# Sensor.net
KiCad netlist of a schematic drawn in Altium Designer
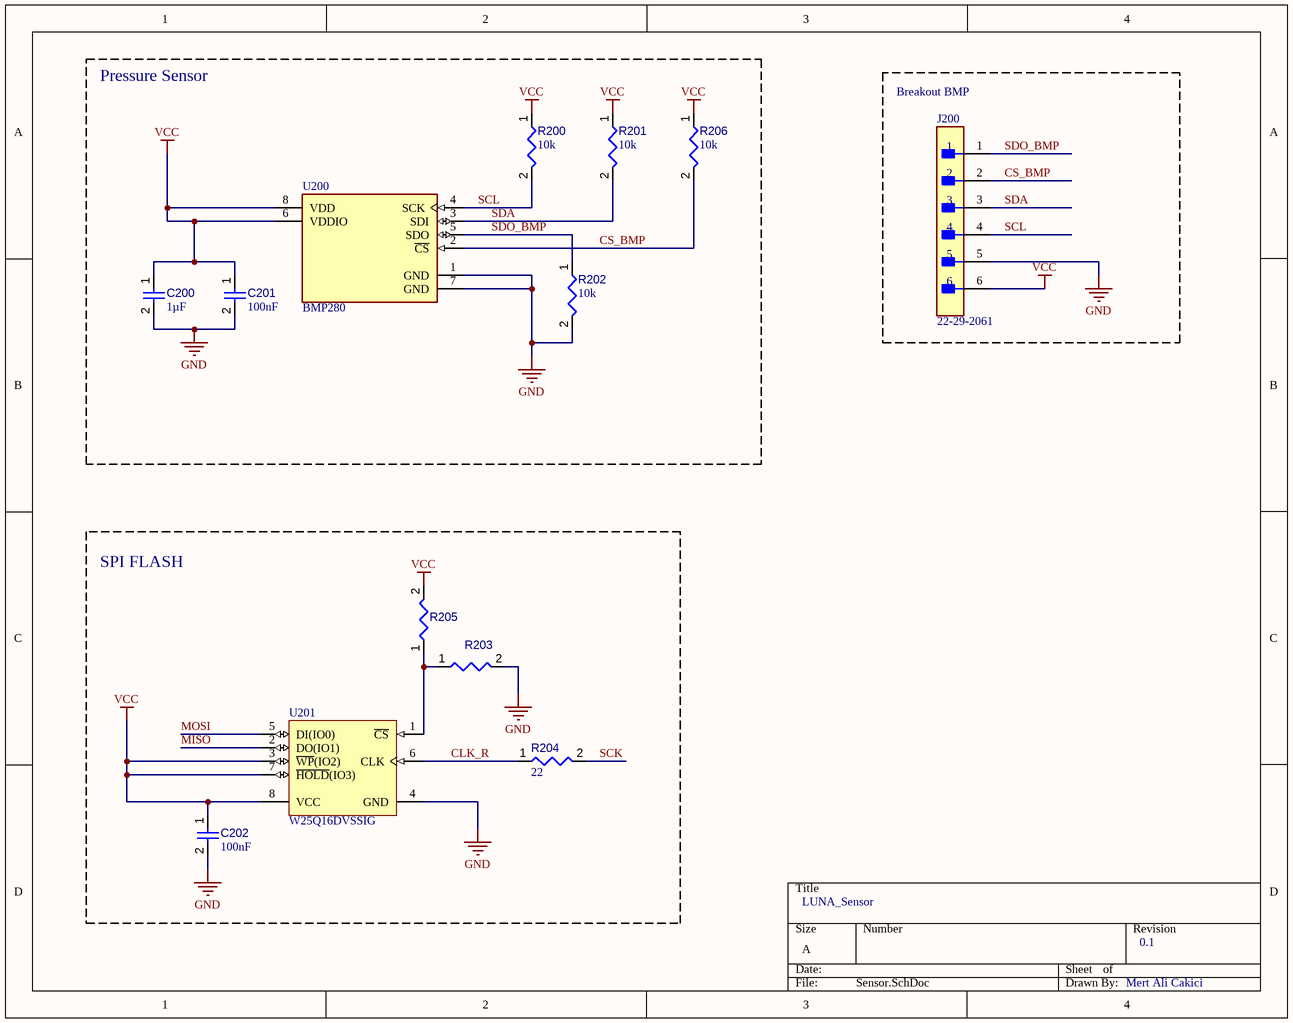
[diagram p0: Sensor.SchDoc]

(export (version "E")
  (design (tool "Eeschema 10.0.6"))
  (components
    (comp (ref "C200")
      (value "1µF")
      (footprint "CAPC1608X90X35NL15T15")
      (description "Chip Capacitor, 1 uF, +/- 10%, 16 V, 0603 (1608 Metric)")
      (fields (field (name "TOLERANCE") "10%") (field (name "Comment") "Capacitor 1uF +/- 10% 16V 0603"))
      (libsource (lib "Mert ALi Çakıcı") (part "CAP-NP-2"))
    )
    (comp (ref "C201")
      (value "100nF")
      (footprint "CAPC1608X90X40NL10T20")
      (description "Chip Capacitor, 100 nF, +/- 10%, 50 V, 0603 (1608 Metric)")
      (fields (field (name "TOLERANCE") "10%") (field (name "Comment") "Capacitor 100 nF +/-10% 50 V 0603"))
      (libsource (lib "Mert ALi Çakıcı") (part "CAP-NP-2"))
    )
    (comp (ref "C202")
      (value "100nF")
      (footprint "CAPC1608X90X40NL10T20")
      (description "Chip Capacitor, 100 nF, +/- 10%, 50 V, 0603 (1608 Metric)")
      (fields (field (name "TOLERANCE") "10%") (field (name "Comment") "Capacitor 100 nF +/-10% 50 V 0603"))
      (libsource (lib "Mert ALi Çakıcı") (part "CAP-NP-2"))
    )
    (comp (ref "J200")
      (value "22-29-2061")
      (footprint "FP-22-29-2061-MFG")
      (description "CONN HEADER VERT 6POS 2.54MM")
      (libsource (lib "Altium Content Vault") (part "f2cb566baf1c37ab5a3b8e90bbeafd6"))
    )
    (comp (ref "R200")
      (value "10k")
      (footprint "RESC1608X55X25NL10T15")
      (description "Chip Resistor, 10 KOhm, +/- 1%, 01 W, -55 to 155 degC, 0603 (1608 Metric)")
      (fields (field (name "POWER") "100mW") (field (name "TOLERANCE") "1%"))
      (libsource (lib "Mert ALi Çakıcı") (part "RES-2"))
    )
    (comp (ref "R201")
      (value "10k")
      (footprint "RESC1608X55X25NL10T15")
      (description "Chip Resistor, 10 KOhm, +/- 1%, 01 W, -55 to 155 degC, 0603 (1608 Metric)")
      (fields (field (name "POWER") "100mW") (field (name "TOLERANCE") "1%"))
      (libsource (lib "Mert ALi Çakıcı") (part "RES-2"))
    )
    (comp (ref "R202")
      (value "10k")
      (footprint "RESC1608X55X25NL10T15")
      (description "Chip Resistor, 10 KOhm, +/- 1%, 01 W, -55 to 155 degC, 0603 (1608 Metric)")
      (fields (field (name "POWER") "100mW") (field (name "TOLERANCE") "1%"))
      (libsource (lib "Mert ALi Çakıcı") (part "RES-2"))
    )
    (comp (ref "R203")
      (value "Jumper 0603")
      (footprint "RESC0603(1608)_L")
      (libsource (lib "Mert ALi Çakıcı") (part "RES-2"))
    )
    (comp (ref "R204")
      (value "22")
      (footprint "RESC1609X50X30ML08T20")
      (description "Chip Resistor, 22 Ohm, +/- 1%, 100 mW, -55 to 155 degC, 0603 (1608 Metric)")
      (fields (field (name "POWER") "100mW") (field (name "TOLERANCE") "1%"))
      (libsource (lib "Mert ALi Çakıcı") (part "RES-2"))
    )
    (comp (ref "R205")
      (value "DNP")
      (footprint "RESC0603(1608)_L")
      (description "Jumper 0603")
      (libsource (lib "Mert ALi Çakıcı") (part "RES-2"))
    )
    (comp (ref "R206")
      (value "10k")
      (footprint "RESC1608X55X25NL10T15")
      (description "Chip Resistor, 10 KOhm, +/- 1%, 01 W, -55 to 155 degC, 0603 (1608 Metric)")
      (fields (field (name "POWER") "100mW") (field (name "TOLERANCE") "1%"))
      (libsource (lib "Mert ALi Çakıcı") (part "RES-2"))
    )
    (comp (ref "U200")
      (value "BMP280")
      (footprint "FP-BMP280-MFG")
      (description "SENSOR PRESSURE ABS")
      (libsource (lib "Altium Content Vault") (part "69b1aacbb03d82763a43fac02afba64"))
    )
    (comp (ref "U201")
      (value "W25Q16DVSSIG")
      (footprint "WINB-W25Q16DVSSIG-8_N")
      (description "IC FLASH 16MBIT 104MHZ 8SOIC")
      (fields (field (name "MANUFACTURER") "Winbond"))
      (libsource (lib "Altium Content Vault") (part "WINB-W25Q16DVSSIG-8"))
    )
  )
  (nets
    (net (code "1") (name "/CLK_R") (class "Default")
      (node (ref "R204") (pin "1") (pinfunction "1_1") (pintype "passive"))
      (node (ref "U201") (pin "6") (pinfunction "CLK_6") (pintype "input"))
    )
    (net (code "2") (name "/CS_BMP") (class "Default")
      (node (ref "J200") (pin "2") (pinfunction "2_2") (pintype "passive"))
      (node (ref "R206") (pin "2") (pinfunction "2_2") (pintype "passive"))
      (node (ref "U200") (pin "2") (pinfunction "~{CS}_2") (pintype "input"))
    )
    (net (code "3") (name "/MISO") (class "Default")
      (node (ref "U201") (pin "2") (pinfunction "DO(IO1)_2") (pintype "bidirectional"))
    )
    (net (code "4") (name "/MOSI") (class "Default")
      (node (ref "U201") (pin "5") (pinfunction "DI(IO0)_5") (pintype "bidirectional"))
    )
    (net (code "5") (name "/SCK") (class "Default")
      (node (ref "R204") (pin "2") (pinfunction "2_2") (pintype "passive"))
    )
    (net (code "6") (name "/SCL") (class "Default")
      (node (ref "J200") (pin "4") (pinfunction "4_4") (pintype "passive"))
      (node (ref "R200") (pin "2") (pinfunction "2_2") (pintype "passive"))
      (node (ref "U200") (pin "4") (pinfunction "SCK_4") (pintype "input"))
    )
    (net (code "7") (name "/SDA") (class "Default")
      (node (ref "J200") (pin "3") (pinfunction "3_3") (pintype "passive"))
      (node (ref "R201") (pin "2") (pinfunction "2_2") (pintype "passive"))
      (node (ref "U200") (pin "3") (pinfunction "SDI_3") (pintype "bidirectional"))
    )
    (net (code "8") (name "/SDO_BMP") (class "Default")
      (node (ref "J200") (pin "1") (pinfunction "1_1") (pintype "passive"))
      (node (ref "R202") (pin "1") (pinfunction "1_1") (pintype "passive"))
      (node (ref "U200") (pin "5") (pinfunction "SDO_5") (pintype "bidirectional"))
    )
    (net (code "9") (name "GND") (class "Default")
      (node (ref "C200") (pin "2") (pinfunction "2_2") (pintype "passive"))
      (node (ref "C201") (pin "2") (pinfunction "2_2") (pintype "passive"))
      (node (ref "C202") (pin "2") (pinfunction "2_2") (pintype "passive"))
      (node (ref "J200") (pin "5") (pinfunction "5_5") (pintype "passive"))
      (node (ref "R202") (pin "2") (pinfunction "2_2") (pintype "passive"))
      (node (ref "R203") (pin "2") (pinfunction "2_2") (pintype "passive"))
      (node (ref "U200") (pin "1") (pinfunction "GND_1") (pintype "power_in"))
      (node (ref "U200") (pin "7") (pinfunction "GND_7") (pintype "power_in"))
      (node (ref "U201") (pin "4") (pinfunction "GND_4") (pintype "power_in"))
    )
    (net (code "10") (name "Net-(U201-~{CS})") (class "Default")
      (node (ref "R203") (pin "1") (pinfunction "1_1") (pintype "passive"))
      (node (ref "R205") (pin "1") (pinfunction "1_1") (pintype "passive"))
      (node (ref "U201") (pin "1") (pinfunction "~{CS}_1") (pintype "input"))
    )
    (net (code "11") (name "VCC") (class "Default")
      (node (ref "C200") (pin "1") (pinfunction "1_1") (pintype "passive"))
      (node (ref "C201") (pin "1") (pinfunction "1_1") (pintype "passive"))
      (node (ref "C202") (pin "1") (pinfunction "1_1") (pintype "passive"))
      (node (ref "J200") (pin "6") (pinfunction "6_6") (pintype "passive"))
      (node (ref "R200") (pin "1") (pinfunction "1_1") (pintype "passive"))
      (node (ref "R201") (pin "1") (pinfunction "1_1") (pintype "passive"))
      (node (ref "R205") (pin "2") (pinfunction "2_2") (pintype "passive"))
      (node (ref "R206") (pin "1") (pinfunction "1_1") (pintype "passive"))
      (node (ref "U200") (pin "6") (pinfunction "VDDIO_6") (pintype "power_in"))
      (node (ref "U200") (pin "8") (pinfunction "VDD_8") (pintype "power_in"))
      (node (ref "U201") (pin "3") (pinfunction "~{WP}(IO2)_3") (pintype "bidirectional"))
      (node (ref "U201") (pin "7") (pinfunction "~{HOLD}(IO3)_7") (pintype "bidirectional"))
      (node (ref "U201") (pin "8") (pinfunction "VCC_8") (pintype "power_in"))
    )
  )
)
